# SCHEMATIC.net
KiCad netlist of a schematic drawn in EAGLE
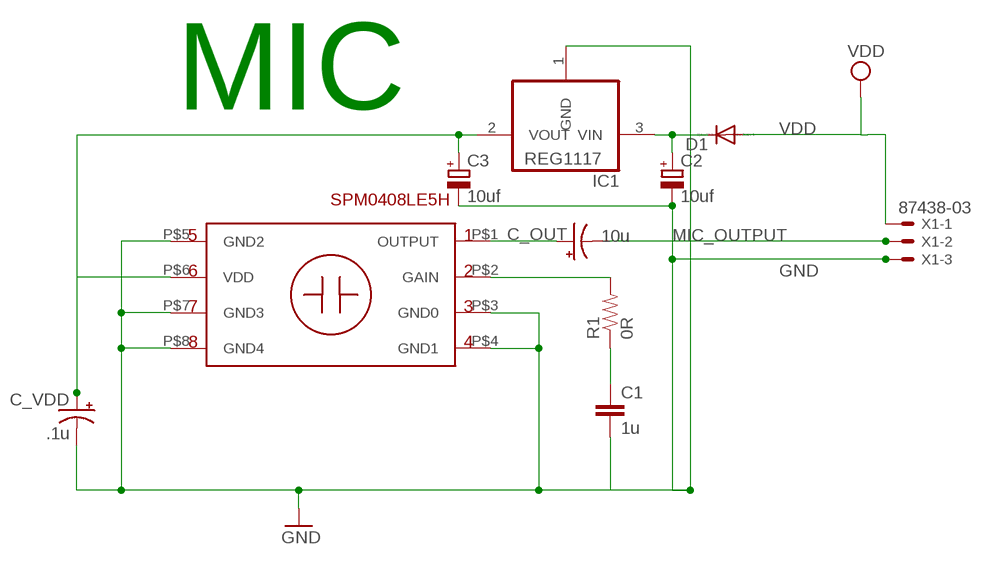
[diagram p0: schematic, sheet 1]

(export (version "E")
  (design (tool "Eeschema 10.0.6"))
  (components
    (comp (ref "C1")
      (value "1u")
      (footprint "eagle-import:0402")
      (libsource (lib "eagle-import") (part "CAP_0402"))
    )
    (comp (ref "C2")
      (value "10uf")
      (footprint "eagle-import:D_7343-31W")
      (libsource (lib "eagle-import") (part "CPOL-EUD/7343-31W"))
    )
    (comp (ref "C3")
      (value "10uf")
      (footprint "eagle-import:D_7343-31W")
      (libsource (lib "eagle-import") (part "CPOL-EUD/7343-31W"))
    )
    (comp (ref "C_OUT")
      (value "10u")
      (footprint "eagle-import:EIA3216-KIT")
      (fields (field (name "MF") "AVX") (field (name "MPN") "0603ZD106MAT2A"))
      (libsource (lib "eagle-import") (part "CAP_POL1206-KIT"))
    )
    (comp (ref "C_VDD")
      (value ".1u")
      (footprint "eagle-import:EIA3216-KIT")
      (fields (field (name "MF") "VISHAY SPRAGUE") (field (name "MPN") "293D106X96R3A2TE3"))
      (libsource (lib "eagle-import") (part "CAP_POL1206-KIT"))
    )
    (comp (ref "D1")
      (value "DIODE-DO214AA")
      (footprint "eagle-import:DO214AA")
      (libsource (lib "eagle-import") (part "DIODE-DO214AA"))
    )
    (comp (ref "IC1")
      (value "REG1117")
      (footprint "eagle-import:SOT223")
      (libsource (lib "eagle-import") (part "REG1117"))
    )
    (comp (ref "R1")
      (value "0R")
      (footprint "eagle-import:0402")
      (libsource (lib "eagle-import") (part "RES_0402"))
    )
    (comp (ref "U2")
      (value "SPM0408LE5H")
      (footprint "eagle-import:SPM0408LE5H-TB")
      (libsource (lib "eagle-import") (part "SPM0408LE5H"))
    )
    (comp (ref "X1")
      (value "87438-03")
      (footprint "eagle-import:87438-03")
      (fields (field (name "MF") "MOLEX"))
      (libsource (lib "eagle-import") (part "87438-03"))
    )
  )
  (nets
    (net (code "1") (name "/MIC_OUTPUT") (class "Default")
      (node (ref "C_OUT") (pin "C") (pinfunction "-_C") (pintype "passive"))
      (node (ref "X1") (pin "2") (pinfunction "S_2") (pintype "passive"))
    )
    (net (code "2") (name "GND") (class "Default")
      (node (ref "C1") (pin "2") (pinfunction "2_2") (pintype "passive"))
      (node (ref "C2") (pin "-") (pinfunction "-_-") (pintype "passive"))
      (node (ref "C3") (pin "-") (pinfunction "-_-") (pintype "passive"))
      (node (ref "C_VDD") (pin "C") (pinfunction "-_C") (pintype "passive"))
      (node (ref "IC1") (pin "1") (pinfunction "GND_1") (pintype "power_in"))
      (node (ref "U2") (pin "P$3") (pinfunction "GND0_P$3") (pintype "power_in"))
      (node (ref "U2") (pin "P$4") (pinfunction "GND1_P$4") (pintype "power_in"))
      (node (ref "U2") (pin "P$5") (pinfunction "GND2_P$5") (pintype "power_in"))
      (node (ref "U2") (pin "P$7") (pinfunction "GND3_P$7") (pintype "power_in"))
      (node (ref "U2") (pin "P$8") (pinfunction "GND4_P$8") (pintype "power_in"))
      (node (ref "X1") (pin "3") (pinfunction "S_3") (pintype "passive"))
    )
    (net (code "3") (name "Net-(C1-Pad1)") (class "Default")
      (node (ref "C1") (pin "1") (pinfunction "1_1") (pintype "passive"))
      (node (ref "R1") (pin "1") (pinfunction "1_1") (pintype "passive"))
    )
    (net (code "4") (name "Net-(C_OUT-+)") (class "Default")
      (node (ref "C_OUT") (pin "A") (pinfunction "+_A") (pintype "passive"))
      (node (ref "U2") (pin "P$1") (pinfunction "OUTPUT_P$1") (pintype "output"))
    )
    (net (code "5") (name "Net-(C_VDD-+)") (class "Default")
      (node (ref "C3") (pin "+") (pinfunction "+_+") (pintype "passive"))
      (node (ref "C_VDD") (pin "A") (pinfunction "+_A") (pintype "passive"))
      (node (ref "IC1") (pin "2") (pinfunction "VOUT_2") (pintype "output"))
      (node (ref "U2") (pin "P$6") (pinfunction "VDD_P$6") (pintype "power_in"))
    )
    (net (code "6") (name "Net-(IC1-VIN)") (class "Default")
      (node (ref "C2") (pin "+") (pinfunction "+_+") (pintype "passive"))
      (node (ref "D1") (pin "C") (pinfunction "C_C") (pintype "passive"))
      (node (ref "IC1") (pin "3") (pinfunction "VIN_3") (pintype "input"))
    )
    (net (code "7") (name "Net-(U2-GAIN)") (class "Default")
      (node (ref "R1") (pin "2") (pinfunction "2_2") (pintype "passive"))
      (node (ref "U2") (pin "P$2") (pinfunction "GAIN_P$2") (pintype "input"))
    )
    (net (code "8") (name "VDD") (class "Default")
      (node (ref "D1") (pin "A") (pinfunction "A_A") (pintype "passive"))
      (node (ref "X1") (pin "1") (pinfunction "S_1") (pintype "passive"))
    )
  )
)
